# 02-mcu0.net
KiCad netlist of a schematic drawn in Altium Designer
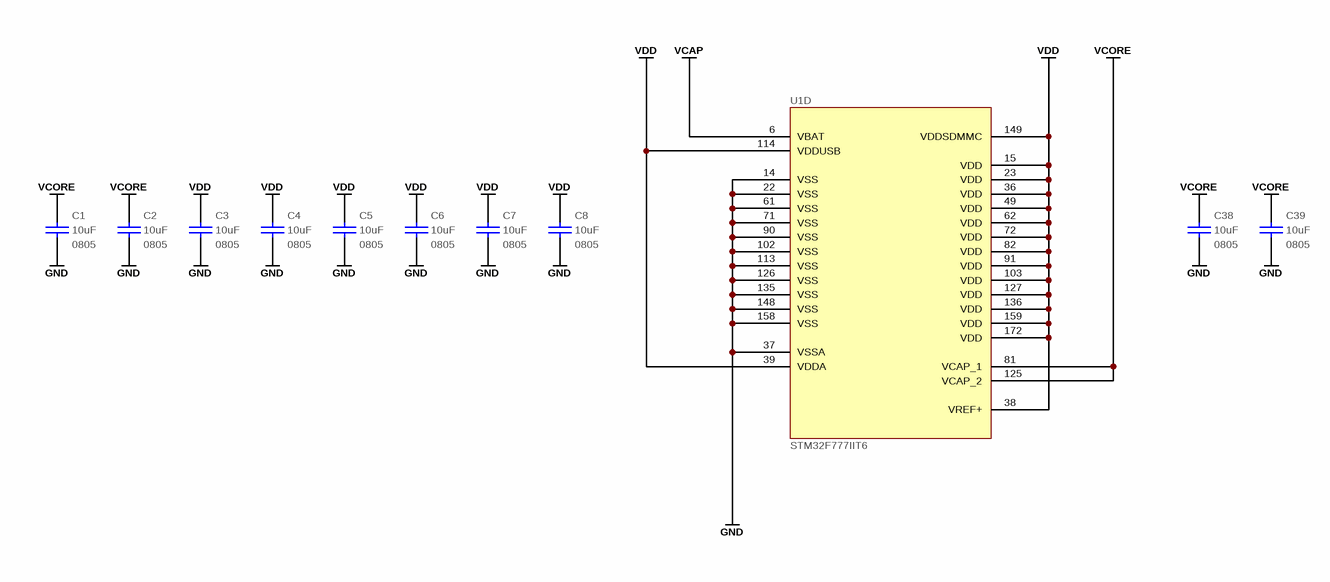
[diagram p0: 02-mcu0.SchDoc]

(export (version "E")
  (design (tool "Eeschema 10.0.6"))
  (components
    (comp (ref "C1")
      (value "10uF")
      (footprint "CAPC200X125X145L45N")
      (description "Ceramic Capacitor 10uF ±10% 16V X7R 0805")
      (fields
        (field (name "MANUFACTURER") "Samsung")
        (field (name "TOLERANCE") "±10%")
        (field (name "PACKAGE") "0805")
      )
      (libsource (lib "capacitors") (part "CAP"))
    )
    (comp (ref "C2")
      (value "10uF")
      (footprint "CAPC200X125X145L45N")
      (description "Ceramic Capacitor 10uF ±10% 16V X7R 0805")
      (fields
        (field (name "MANUFACTURER") "Samsung")
        (field (name "TOLERANCE") "±10%")
        (field (name "PACKAGE") "0805")
      )
      (libsource (lib "capacitors") (part "CAP"))
    )
    (comp (ref "C3")
      (value "10uF")
      (footprint "CAPC200X125X145L45N")
      (description "Ceramic Capacitor 10uF ±10% 16V X7R 0805")
      (fields
        (field (name "MANUFACTURER") "Samsung")
        (field (name "TOLERANCE") "±10%")
        (field (name "PACKAGE") "0805")
      )
      (libsource (lib "capacitors") (part "CAP"))
    )
    (comp (ref "C4")
      (value "10uF")
      (footprint "CAPC200X125X145L45N")
      (description "Ceramic Capacitor 10uF ±10% 16V X7R 0805")
      (fields
        (field (name "MANUFACTURER") "Samsung")
        (field (name "TOLERANCE") "±10%")
        (field (name "PACKAGE") "0805")
      )
      (libsource (lib "capacitors") (part "CAP"))
    )
    (comp (ref "C5")
      (value "10uF")
      (footprint "CAPC200X125X145L45N")
      (description "Ceramic Capacitor 10uF ±10% 16V X7R 0805")
      (fields
        (field (name "MANUFACTURER") "Samsung")
        (field (name "TOLERANCE") "±10%")
        (field (name "PACKAGE") "0805")
      )
      (libsource (lib "capacitors") (part "CAP"))
    )
    (comp (ref "C6")
      (value "10uF")
      (footprint "CAPC200X125X145L45N")
      (description "Ceramic Capacitor 10uF ±10% 16V X7R 0805")
      (fields
        (field (name "MANUFACTURER") "Samsung")
        (field (name "TOLERANCE") "±10%")
        (field (name "PACKAGE") "0805")
      )
      (libsource (lib "capacitors") (part "CAP"))
    )
    (comp (ref "C7")
      (value "10uF")
      (footprint "CAPC200X125X145L45N")
      (description "Ceramic Capacitor 10uF ±10% 16V X7R 0805")
      (fields
        (field (name "MANUFACTURER") "Samsung")
        (field (name "TOLERANCE") "±10%")
        (field (name "PACKAGE") "0805")
      )
      (libsource (lib "capacitors") (part "CAP"))
    )
    (comp (ref "C8")
      (value "10uF")
      (footprint "CAPC200X125X145L45N")
      (description "Ceramic Capacitor 10uF ±10% 16V X7R 0805")
      (fields
        (field (name "MANUFACTURER") "Samsung")
        (field (name "TOLERANCE") "±10%")
        (field (name "PACKAGE") "0805")
      )
      (libsource (lib "capacitors") (part "CAP"))
    )
    (comp (ref "C38")
      (value "10uF")
      (footprint "CAPC200X125X145L45N")
      (description "Ceramic Capacitor 10uF ±10% 16V X7R 0805")
      (fields
        (field (name "MANUFACTURER") "Samsung")
        (field (name "TOLERANCE") "±10%")
        (field (name "PACKAGE") "0805")
      )
      (libsource (lib "capacitors") (part "CAP"))
    )
    (comp (ref "C39")
      (value "10uF")
      (footprint "CAPC200X125X145L45N")
      (description "Ceramic Capacitor 10uF ±10% 16V X7R 0805")
      (fields
        (field (name "MANUFACTURER") "Samsung")
        (field (name "TOLERANCE") "±10%")
        (field (name "PACKAGE") "0805")
      )
      (libsource (lib "capacitors") (part "CAP"))
    )
    (comp (ref "U1")
      (value "STM32F777IIT6")
      (footprint "st:TSQFP50P2600X2600X160-176N")
      (description "Microcontroller")
      (fields (field (name "MANUFACTURER") "STMicroelectronics"))
      (libsource (lib "st") (part "STM32F777IIT"))
    )
  )
  (nets
    (net (code "1") (name "GND") (class "Default")
      (node (ref "C1") (pin "2") (pinfunction "2_2") (pintype "passive"))
      (node (ref "C2") (pin "2") (pinfunction "2_2") (pintype "passive"))
      (node (ref "C3") (pin "2") (pinfunction "2_2") (pintype "passive"))
      (node (ref "C38") (pin "2") (pinfunction "2_2") (pintype "passive"))
      (node (ref "C39") (pin "2") (pinfunction "2_2") (pintype "passive"))
      (node (ref "C4") (pin "2") (pinfunction "2_2") (pintype "passive"))
      (node (ref "C5") (pin "2") (pinfunction "2_2") (pintype "passive"))
      (node (ref "C6") (pin "2") (pinfunction "2_2") (pintype "passive"))
      (node (ref "C7") (pin "2") (pinfunction "2_2") (pintype "passive"))
      (node (ref "C8") (pin "2") (pinfunction "2_2") (pintype "passive"))
      (node (ref "U1") (pin "102") (pinfunction "VSS_102") (pintype "power_in"))
      (node (ref "U1") (pin "113") (pinfunction "VSS_113") (pintype "power_in"))
      (node (ref "U1") (pin "126") (pinfunction "VSS_126") (pintype "power_in"))
      (node (ref "U1") (pin "135") (pinfunction "VSS_135") (pintype "power_in"))
      (node (ref "U1") (pin "14") (pinfunction "VSS_14") (pintype "power_in"))
      (node (ref "U1") (pin "148") (pinfunction "VSS_148") (pintype "power_in"))
      (node (ref "U1") (pin "158") (pinfunction "VSS_158") (pintype "power_in"))
      (node (ref "U1") (pin "22") (pinfunction "VSS_22") (pintype "power_in"))
      (node (ref "U1") (pin "37") (pinfunction "VSSA_37") (pintype "power_in"))
      (node (ref "U1") (pin "61") (pinfunction "VSS_61") (pintype "power_in"))
      (node (ref "U1") (pin "71") (pinfunction "VSS_71") (pintype "power_in"))
      (node (ref "U1") (pin "90") (pinfunction "VSS_90") (pintype "power_in"))
    )
    (net (code "2") (name "VCAP") (class "Default")
      (node (ref "U1") (pin "6") (pinfunction "VBAT_6") (pintype "power_in"))
    )
    (net (code "3") (name "VCORE") (class "Default")
      (node (ref "C1") (pin "1") (pinfunction "1_1") (pintype "passive"))
      (node (ref "C2") (pin "1") (pinfunction "1_1") (pintype "passive"))
      (node (ref "C38") (pin "1") (pinfunction "1_1") (pintype "passive"))
      (node (ref "C39") (pin "1") (pinfunction "1_1") (pintype "passive"))
      (node (ref "U1") (pin "125") (pinfunction "VCAP_2_125") (pintype "power_in"))
      (node (ref "U1") (pin "81") (pinfunction "VCAP_1_81") (pintype "power_in"))
    )
    (net (code "4") (name "VDD") (class "Default")
      (node (ref "C3") (pin "1") (pinfunction "1_1") (pintype "passive"))
      (node (ref "C4") (pin "1") (pinfunction "1_1") (pintype "passive"))
      (node (ref "C5") (pin "1") (pinfunction "1_1") (pintype "passive"))
      (node (ref "C6") (pin "1") (pinfunction "1_1") (pintype "passive"))
      (node (ref "C7") (pin "1") (pinfunction "1_1") (pintype "passive"))
      (node (ref "C8") (pin "1") (pinfunction "1_1") (pintype "passive"))
      (node (ref "U1") (pin "103") (pinfunction "VDD_103") (pintype "power_in"))
      (node (ref "U1") (pin "114") (pinfunction "VDDUSB_114") (pintype "power_in"))
      (node (ref "U1") (pin "127") (pinfunction "VDD_127") (pintype "power_in"))
      (node (ref "U1") (pin "136") (pinfunction "VDD_136") (pintype "power_in"))
      (node (ref "U1") (pin "149") (pinfunction "VDDSDMMC_149") (pintype "power_in"))
      (node (ref "U1") (pin "15") (pinfunction "VDD_15") (pintype "power_in"))
      (node (ref "U1") (pin "159") (pinfunction "VDD_159") (pintype "power_in"))
      (node (ref "U1") (pin "172") (pinfunction "VDD_172") (pintype "power_in"))
      (node (ref "U1") (pin "23") (pinfunction "VDD_23") (pintype "power_in"))
      (node (ref "U1") (pin "36") (pinfunction "VDD_36") (pintype "power_in"))
      (node (ref "U1") (pin "38") (pinfunction "VREF+_38") (pintype "power_in"))
      (node (ref "U1") (pin "39") (pinfunction "VDDA_39") (pintype "power_in"))
      (node (ref "U1") (pin "49") (pinfunction "VDD_49") (pintype "power_in"))
      (node (ref "U1") (pin "62") (pinfunction "VDD_62") (pintype "power_in"))
      (node (ref "U1") (pin "72") (pinfunction "VDD_72") (pintype "power_in"))
      (node (ref "U1") (pin "82") (pinfunction "VDD_82") (pintype "power_in"))
      (node (ref "U1") (pin "91") (pinfunction "VDD_91") (pintype "power_in"))
    )
  )
)
